# ProDoc_TweenWave_2026-01-04.net
KiCad netlist of a schematic drawn in EasyEDA Pro
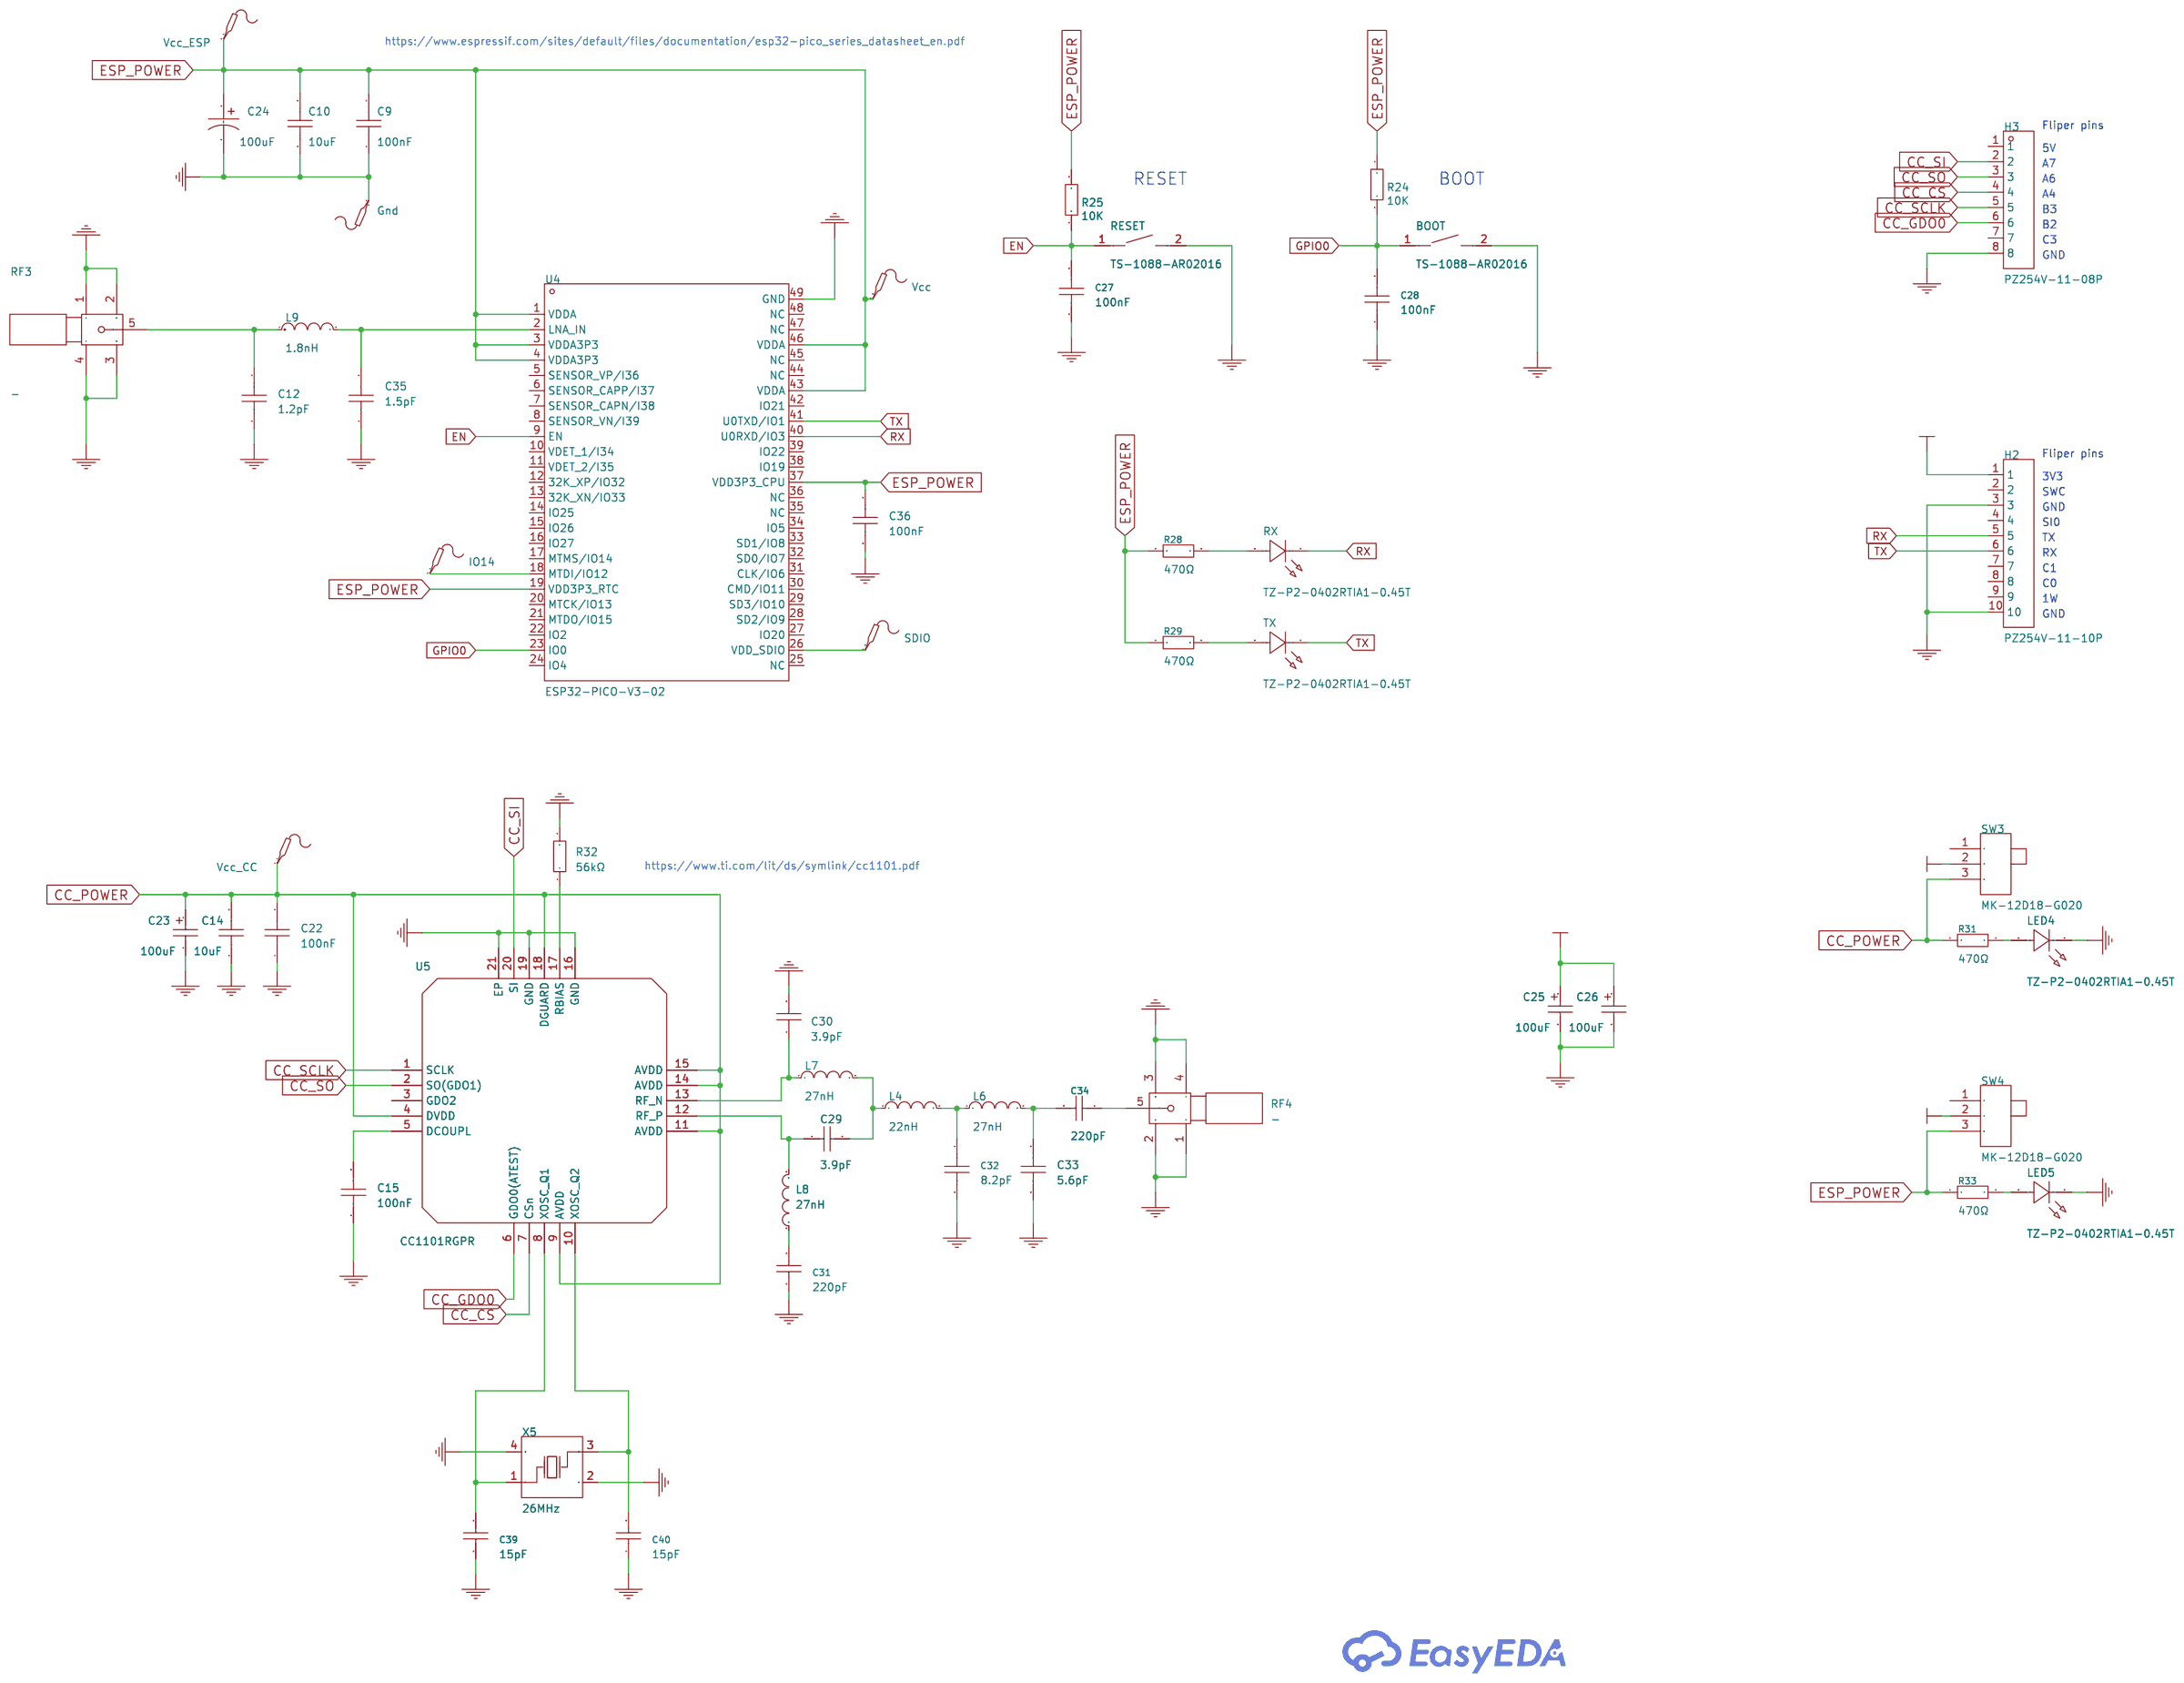
[diagram p0: schematic sheet]

(export (version "E")
  (design (tool "Eeschema 10.0.6"))
  (components
    (comp (ref "BOOT")
      (value "TS-1088-AR02016")
      (footprint "easyedapro:SW-SMD_L3.9-W3.0-P4.45")
      (fields (field (name "Manufacturer") "XUNPU(讯普)"))
      (libsource (lib "easyedapro") (part "TS-1088-AR02016"))
    )
    (comp (ref "C9")
      (value "100nF")
      (footprint "easyedapro:C0603")
      (description "Capacitance:100nF Tolerance:±10% Tolerance:±10% Voltage Rating:50V Temperature Coefficient:X7R")
      (fields
        (field (name "Manufacturer Part") "CC0603KRX7R9BB104")
        (field (name "Manufacturer") "YAGEO(国巨)")
      )
      (libsource (lib "easyedapro") (part "CC0603KRX7R9BB104"))
    )
    (comp (ref "C10")
      (value "10uF")
      (footprint "easyedapro:C0603")
      (fields
        (field (name "Manufacturer Part") "CL10A106MP8NNNC")
        (field (name "Manufacturer") "SAMSUNG(三星)")
      )
      (libsource (lib "easyedapro") (part "CL10A106MP8NNNC"))
    )
    (comp (ref "C12")
      (value "1.2pF")
      (footprint "easyedapro:C0201")
      (fields
        (field (name "Manufacturer Part") "GRM0335C1H1R2BA01D")
        (field (name "Manufacturer") "muRata(村田)")
      )
      (libsource (lib "easyedapro") (part "GRM0335C1H1R2BA01D"))
    )
    (comp (ref "C14")
      (value "10uF")
      (footprint "easyedapro:C0603")
      (fields
        (field (name "Manufacturer Part") "CL10A106MP8NNNC")
        (field (name "Manufacturer") "SAMSUNG(三星)")
      )
      (libsource (lib "easyedapro") (part "CL10A106MP8NNNC"))
    )
    (comp (ref "C15")
      (value "100nF")
      (footprint "easyedapro:C0603")
      (description "Capacitance:100nF Tolerance:±10% Tolerance:±10% Voltage Rating:50V Temperature Coefficient:X7R")
      (fields
        (field (name "Manufacturer Part") "CC0603KRX7R9BB104")
        (field (name "Manufacturer") "YAGEO(国巨)")
      )
      (libsource (lib "easyedapro") (part "CC0603KRX7R9BB104"))
    )
    (comp (ref "C22")
      (value "100nF")
      (footprint "easyedapro:C0603")
      (description "Capacitance:100nF Tolerance:±10% Tolerance:±10% Voltage Rating:50V Temperature Coefficient:X7R")
      (fields
        (field (name "Manufacturer Part") "CC0603KRX7R9BB104")
        (field (name "Manufacturer") "YAGEO(国巨)")
      )
      (libsource (lib "easyedapro") (part "CC0603KRX7R9BB104"))
    )
    (comp (ref "C23")
      (value "100uF")
      (footprint "easyedapro:CASE-B_3528")
      (fields (field (name "Manufacturer Part") "TAJB107K006RNJ") (field (name "Manufacturer") "Kyocera AVX"))
      (libsource (lib "easyedapro") (part "TAJB107K006RNJ"))
    )
    (comp (ref "C24")
      (value "100uF")
      (footprint "easyedapro:CASE-B_3528-1")
      (fields
        (field (name "Manufacturer Part") "TPSB107K006R0250")
        (field (name "Manufacturer") "Kyocera AVX")
      )
      (libsource (lib "easyedapro") (part "TPSB107K006R0250"))
    )
    (comp (ref "C25")
      (value "100uF")
      (footprint "easyedapro:CASE-B_3528")
      (fields (field (name "Manufacturer Part") "TAJB107K006RNJ") (field (name "Manufacturer") "Kyocera AVX"))
      (libsource (lib "easyedapro") (part "TAJB107K006RNJ"))
    )
    (comp (ref "C26")
      (value "100uF")
      (footprint "easyedapro:CASE-B_3528")
      (fields (field (name "Manufacturer Part") "TAJB107K006RNJ") (field (name "Manufacturer") "Kyocera AVX"))
      (libsource (lib "easyedapro") (part "TAJB107K006RNJ"))
    )
    (comp (ref "C27")
      (value "100nF")
      (footprint "easyedapro:C0402")
      (fields
        (field (name "Manufacturer Part") "CC0402KRX7R7BB104")
        (field (name "Manufacturer") "YAGEO(国巨)")
      )
      (libsource (lib "easyedapro") (part "CC0402KRX7R7BB104"))
    )
    (comp (ref "C28")
      (value "100nF")
      (footprint "easyedapro:C0402")
      (fields
        (field (name "Manufacturer Part") "CC0402KRX7R7BB104")
        (field (name "Manufacturer") "YAGEO(国巨)")
      )
      (libsource (lib "easyedapro") (part "CC0402KRX7R7BB104"))
    )
    (comp (ref "C29")
      (value "3.9pF")
      (footprint "easyedapro:C0402")
      (fields (field (name "Manufacturer Part") "0402CG3R9C500NT") (field (name "Manufacturer") "FH(风华)"))
      (libsource (lib "easyedapro") (part "0402CG3R9C500NT"))
    )
    (comp (ref "C30")
      (value "3.9pF")
      (footprint "easyedapro:C0402")
      (fields (field (name "Manufacturer Part") "0402CG3R9C500NT") (field (name "Manufacturer") "FH(风华)"))
      (libsource (lib "easyedapro") (part "0402CG3R9C500NT"))
    )
    (comp (ref "C31")
      (value "220pF")
      (footprint "easyedapro:C0402")
      (description "Capacitance:220pF Tolerance:±5% Tolerance:±5% Voltage Rating:50V Temperature Coefficient:NP0")
      (fields
        (field (name "Manufacturer Part") "CC0402JRNPO9BN221")
        (field (name "Manufacturer") "YAGEO(国巨)")
      )
      (libsource (lib "easyedapro") (part "CC0402JRNPO9BN221"))
    )
    (comp (ref "C32")
      (value "8.2pF")
      (footprint "easyedapro:C0402")
      (fields
        (field (name "Manufacturer Part") "CC0402BRNPO9BN8R2")
        (field (name "Manufacturer") "YAGEO(国巨)")
      )
      (libsource (lib "easyedapro") (part "CC0402BRNPO9BN8R2"))
    )
    (comp (ref "C33")
      (value "5.6pF")
      (footprint "easyedapro:C0402")
      (fields
        (field (name "Manufacturer Part") "CC0402BRNPO9BN5R6")
        (field (name "Manufacturer") "YAGEO(国巨)")
      )
      (libsource (lib "easyedapro") (part "CC0402BRNPO9BN5R6"))
    )
    (comp (ref "C34")
      (value "220pF")
      (footprint "easyedapro:C0402")
      (description "Capacitance:220pF Tolerance:±5% Tolerance:±5% Voltage Rating:50V Temperature Coefficient:NP0")
      (fields
        (field (name "Manufacturer Part") "CC0402JRNPO9BN221")
        (field (name "Manufacturer") "YAGEO(国巨)")
      )
      (libsource (lib "easyedapro") (part "CC0402JRNPO9BN221"))
    )
    (comp (ref "C35")
      (value "1.5pF")
      (footprint "easyedapro:C0201")
      (fields
        (field (name "Manufacturer Part") "GRM0335C1H1R5BA01D")
        (field (name "Manufacturer") "muRata(村田)")
      )
      (libsource (lib "easyedapro") (part "GRM0335C1H1R5BA01D"))
    )
    (comp (ref "C36")
      (value "100nF")
      (footprint "easyedapro:C0603")
      (description "Capacitance:100nF Tolerance:±10% Tolerance:±10% Voltage Rating:50V Temperature Coefficient:X7R")
      (fields
        (field (name "Manufacturer Part") "CC0603KRX7R9BB104")
        (field (name "Manufacturer") "YAGEO(国巨)")
      )
      (libsource (lib "easyedapro") (part "CC0603KRX7R9BB104"))
    )
    (comp (ref "C39")
      (value "15pF")
      (footprint "easyedapro:C0402")
      (fields
        (field (name "Manufacturer Part") "CC0402JRNPO9BN150")
        (field (name "Manufacturer") "YAGEO(国巨)")
      )
      (libsource (lib "easyedapro") (part "CC0402JRNPO9BN150"))
    )
    (comp (ref "C40")
      (value "15pF")
      (footprint "easyedapro:C0402")
      (fields
        (field (name "Manufacturer Part") "CC0402JRNPO9BN150")
        (field (name "Manufacturer") "YAGEO(国巨)")
      )
      (libsource (lib "easyedapro") (part "CC0402JRNPO9BN150"))
    )
    (comp (ref "Gnd")
      (value "~")
      (footprint "easyedapro:Test-Point-0.5mm")
      (description "Test Point 测试点")
      (libsource (lib "easyedapro") (part "Test-Point"))
    )
    (comp (ref "H2")
      (value "PZ254V-11-10P")
      (footprint "easyedapro:HDR-TH_10P-P2.54-V-M")
      (fields (field (name "Manufacturer") "XFCN(兴飞)"))
      (libsource (lib "easyedapro") (part "PZ254V-11-10P"))
    )
    (comp (ref "H3")
      (value "PZ254V-11-08P")
      (footprint "easyedapro:HDR-TH_8P-P2.54-V-M")
      (fields (field (name "Manufacturer") "XFCN(兴飞)"))
      (libsource (lib "easyedapro") (part "PZ254V-11-08P"))
    )
    (comp (ref "IO14")
      (value "~")
      (footprint "easyedapro:Test-Point-0.5mm")
      (description "Test Point 测试点")
      (libsource (lib "easyedapro") (part "Test-Point"))
    )
    (comp (ref "L4")
      (value "22nH")
      (footprint "easyedapro:L0402")
      (fields (field (name "Manufacturer Part") "LQG15HS22NJ02D") (field (name "Manufacturer") "muRata(村田)"))
      (libsource (lib "easyedapro") (part "LQG15HS22NJ02D"))
    )
    (comp (ref "L6")
      (value "27nH")
      (footprint "easyedapro:L0402-RD")
      (fields (field (name "Manufacturer Part") "LQG15HS27NJ02D") (field (name "Manufacturer") "muRata(村田)"))
      (libsource (lib "easyedapro") (part "LQG15HS27NJ02D"))
    )
    (comp (ref "L7")
      (value "27nH")
      (footprint "easyedapro:L0402-RD")
      (fields (field (name "Manufacturer Part") "LQG15HS27NJ02D") (field (name "Manufacturer") "muRata(村田)"))
      (libsource (lib "easyedapro") (part "LQG15HS27NJ02D"))
    )
    (comp (ref "L8")
      (value "27nH")
      (footprint "easyedapro:L0402-RD")
      (fields (field (name "Manufacturer Part") "LQG15HS27NJ02D") (field (name "Manufacturer") "muRata(村田)"))
      (libsource (lib "easyedapro") (part "LQG15HS27NJ02D"))
    )
    (comp (ref "L9")
      (value "1.8nH")
      (footprint "easyedapro:L0201-RD")
      (fields (field (name "Manufacturer Part") "LQP03TN1N8B02D") (field (name "Manufacturer") "muRata(村田)"))
      (libsource (lib "easyedapro") (part "LQP03TN1N8B02D"))
    )
    (comp (ref "LED4")
      (value "TZ-P2-0402RTIA1-0.45T")
      (footprint "easyedapro:LED0402-RD_RED")
      (fields (field (name "Manufacturer") "TUOZHAN(拓展光电)"))
      (libsource (lib "easyedapro") (part "TZ-P2-0402RTIA1-0.45T"))
    )
    (comp (ref "LED5")
      (value "TZ-P2-0402RTIA1-0.45T")
      (footprint "easyedapro:LED0402-RD_RED")
      (fields (field (name "Manufacturer") "TUOZHAN(拓展光电)"))
      (libsource (lib "easyedapro") (part "TZ-P2-0402RTIA1-0.45T"))
    )
    (comp (ref "R24")
      (value "10K")
      (footprint "easyedapro:R0603")
      (fields (field (name "Manufacturer Part") "RC0603DR-0710KL") (field (name "Manufacturer") "YAGEO(国巨)"))
      (libsource (lib "easyedapro") (part "10K"))
    )
    (comp (ref "R25")
      (value "10K")
      (footprint "easyedapro:R0603")
      (fields (field (name "Manufacturer Part") "RC0603DR-0710KL") (field (name "Manufacturer") "YAGEO(国巨)"))
      (libsource (lib "easyedapro") (part "10K"))
    )
    (comp (ref "R28")
      (value "470Ω")
      (footprint "easyedapro:R0402")
      (fields
        (field (name "Manufacturer Part") "0402WGF4700TCE")
        (field (name "Manufacturer") "UNI-ROYAL(厚声)")
      )
      (libsource (lib "easyedapro") (part "0402WGF4700TCE"))
    )
    (comp (ref "R29")
      (value "470Ω")
      (footprint "easyedapro:R0402")
      (fields
        (field (name "Manufacturer Part") "0402WGF4700TCE")
        (field (name "Manufacturer") "UNI-ROYAL(厚声)")
      )
      (libsource (lib "easyedapro") (part "0402WGF4700TCE"))
    )
    (comp (ref "R31")
      (value "470Ω")
      (footprint "easyedapro:R0402")
      (fields
        (field (name "Manufacturer Part") "0402WGF4700TCE")
        (field (name "Manufacturer") "UNI-ROYAL(厚声)")
      )
      (libsource (lib "easyedapro") (part "0402WGF4700TCE"))
    )
    (comp (ref "R32")
      (value "56kΩ")
      (footprint "easyedapro:R0402")
      (fields
        (field (name "Manufacturer Part") "0402WGF5602TCE")
        (field (name "Manufacturer") "UNI-ROYAL(厚声)")
      )
      (libsource (lib "easyedapro") (part "0402WGF5602TCE"))
    )
    (comp (ref "R33")
      (value "470Ω")
      (footprint "easyedapro:R0402")
      (fields
        (field (name "Manufacturer Part") "0402WGF4700TCE")
        (field (name "Manufacturer") "UNI-ROYAL(厚声)")
      )
      (libsource (lib "easyedapro") (part "0402WGF4700TCE"))
    )
    (comp (ref "RESET")
      (value "TS-1088-AR02016")
      (footprint "easyedapro:SW-SMD_L3.9-W3.0-P4.45")
      (fields (field (name "Manufacturer") "XUNPU(讯普)"))
      (libsource (lib "easyedapro") (part "TS-1088-AR02016"))
    )
    (comp (ref "RF3")
      (value "-")
      (footprint "easyedapro:SMA-SMD_BWSMA-KE-P001")
      (fields
        (field (name "Manufacturer Part") "BWSMA-KE-P001")
        (field (name "Manufacturer") "BAT WIRELESS(蝙蝠无线)")
      )
      (libsource (lib "easyedapro") (part "BWSMA-KE-P001"))
    )
    (comp (ref "RF4")
      (value "-")
      (footprint "easyedapro:SMA-SMD_BWSMA-KE-P001")
      (fields
        (field (name "Manufacturer Part") "BWSMA-KE-P001")
        (field (name "Manufacturer") "BAT WIRELESS(蝙蝠无线)")
      )
      (libsource (lib "easyedapro") (part "BWSMA-KE-P001"))
    )
    (comp (ref "RX")
      (value "TZ-P2-0402RTIA1-0.45T")
      (footprint "easyedapro:LED0402-RD_RED")
      (fields (field (name "Manufacturer") "TUOZHAN(拓展光电)"))
      (libsource (lib "easyedapro") (part "TZ-P2-0402RTIA1-0.45T"))
    )
    (comp (ref "SDIO")
      (value "~")
      (footprint "easyedapro:Test-Point-0.5mm")
      (description "Test Point 测试点")
      (libsource (lib "easyedapro") (part "Test-Point"))
    )
    (comp (ref "SW3")
      (value "MK-12D18-G020")
      (footprint "easyedapro:SW-TH_MK-12D18-G040")
      (fields (field (name "Manufacturer") "G-Switch(品赞)"))
      (libsource (lib "easyedapro") (part "MK-12D18-G020"))
    )
    (comp (ref "SW4")
      (value "MK-12D18-G020")
      (footprint "easyedapro:SW-TH_MK-12D18-G040")
      (fields (field (name "Manufacturer") "G-Switch(品赞)"))
      (libsource (lib "easyedapro") (part "MK-12D18-G020"))
    )
    (comp (ref "TX")
      (value "TZ-P2-0402RTIA1-0.45T")
      (footprint "easyedapro:LED0402-RD_RED")
      (fields (field (name "Manufacturer") "TUOZHAN(拓展光电)"))
      (libsource (lib "easyedapro") (part "TZ-P2-0402RTIA1-0.45T"))
    )
    (comp (ref "U4")
      (value "ESP32-PICO-V3-02")
      (footprint "easyedapro:QFN-48_L7.0-W7.0-P0.50-BL-EP5.1")
      (fields (field (name "Manufacturer") "ESPRESSIF(乐鑫)"))
      (libsource (lib "easyedapro") (part "ESP32-PICO-V3-02"))
    )
    (comp (ref "U5")
      (value "CC1101RGPR")
      (footprint "easyedapro:QFN-20_L4.0-W4.0-P0.5-TL-EP")
      (fields (field (name "Manufacturer") "TI(德州仪器)"))
      (libsource (lib "easyedapro") (part "CC1101RGPR"))
    )
    (comp (ref "Vcc")
      (value "~")
      (footprint "easyedapro:Test-Point-0.5mm")
      (description "Test Point 测试点")
      (libsource (lib "easyedapro") (part "Test-Point"))
    )
    (comp (ref "Vcc_CC")
      (value "~")
      (footprint "easyedapro:Test-Point-0.5mm")
      (description "Test Point 测试点")
      (libsource (lib "easyedapro") (part "Test-Point"))
    )
    (comp (ref "Vcc_ESP")
      (value "~")
      (footprint "easyedapro:Test-Point-0.5mm")
      (description "Test Point 测试点")
      (libsource (lib "easyedapro") (part "Test-Point"))
    )
    (comp (ref "X5")
      (value "26MHz")
      (footprint "easyedapro:CRYSTAL-SMD_4P-L3.2-W2.5-BL")
      (fields (field (name "Manufacturer Part") "X322526MMB4SI") (field (name "Manufacturer") "YXC(扬兴晶振)"))
      (libsource (lib "easyedapro") (part "X322526MMB4SI"))
    )
  )
  (nets
    (net (code "1") (name "3V3") (class "Default")
      (node (ref "C25") (pin "1") (pinfunction "1_1") (pintype "input"))
      (node (ref "C26") (pin "1") (pinfunction "1_1") (pintype "input"))
      (node (ref "H2") (pin "1") (pinfunction "1_1") (pintype "unspecified"))
      (node (ref "SW3") (pin "2") (pinfunction "2_2") (pintype "unspecified"))
      (node (ref "SW4") (pin "2") (pinfunction "2_2") (pintype "unspecified"))
    )
    (net (code "2") (name "CC_CS") (class "Default")
      (node (ref "H3") (pin "4") (pinfunction "4_4") (pintype "unspecified"))
      (node (ref "U5") (pin "7") (pinfunction "CSn_7") (pintype "unspecified"))
    )
    (net (code "3") (name "CC_GDO0") (class "Default")
      (node (ref "H3") (pin "6") (pinfunction "6_6") (pintype "unspecified"))
      (node (ref "U5") (pin "6") (pinfunction "GDO0(ATEST)_6") (pintype "unspecified"))
    )
    (net (code "4") (name "CC_POWER") (class "Default")
      (node (ref "C14") (pin "2") (pinfunction "2_2") (pintype "unspecified"))
      (node (ref "C22") (pin "2") (pinfunction "2_2") (pintype "unspecified"))
      (node (ref "C23") (pin "1") (pinfunction "1_1") (pintype "input"))
      (node (ref "R31") (pin "1") (pinfunction "1_1") (pintype "input"))
      (node (ref "SW3") (pin "3") (pinfunction "3_3") (pintype "unspecified"))
      (node (ref "U5") (pin "11") (pinfunction "AVDD_11") (pintype "unspecified"))
      (node (ref "U5") (pin "14") (pinfunction "AVDD_14") (pintype "unspecified"))
      (node (ref "U5") (pin "15") (pinfunction "AVDD_15") (pintype "unspecified"))
      (node (ref "U5") (pin "18") (pinfunction "DGUARD_18") (pintype "unspecified"))
      (node (ref "U5") (pin "4") (pinfunction "DVDD_4") (pintype "unspecified"))
      (node (ref "U5") (pin "9") (pinfunction "AVDD_9") (pintype "unspecified"))
      (node (ref "Vcc_CC") (pin "1") (pinfunction "1_1") (pintype "unspecified"))
    )
    (net (code "5") (name "CC_SCLK") (class "Default")
      (node (ref "H3") (pin "5") (pinfunction "5_5") (pintype "unspecified"))
      (node (ref "U5") (pin "1") (pinfunction "SCLK_1") (pintype "unspecified"))
    )
    (net (code "6") (name "CC_SI") (class "Default")
      (node (ref "H3") (pin "2") (pinfunction "2_2") (pintype "unspecified"))
      (node (ref "U5") (pin "20") (pinfunction "SI_20") (pintype "unspecified"))
    )
    (net (code "7") (name "CC_SO") (class "Default")
      (node (ref "H3") (pin "3") (pinfunction "3_3") (pintype "unspecified"))
      (node (ref "U5") (pin "2") (pinfunction "SO(GDO1)_2") (pintype "unspecified"))
    )
    (net (code "8") (name "EN") (class "Default")
      (node (ref "C27") (pin "2") (pinfunction "2_2") (pintype "input"))
      (node (ref "R25") (pin "1") (pinfunction "1_1") (pintype "input"))
      (node (ref "RESET") (pin "1") (pinfunction "1_1") (pintype "unspecified"))
      (node (ref "U4") (pin "9") (pinfunction "EN_9") (pintype "unspecified"))
    )
    (net (code "9") (name "ESP_POWER") (class "Default")
      (node (ref "C10") (pin "2") (pinfunction "2_2") (pintype "unspecified"))
      (node (ref "C24") (pin "1") (pinfunction "1_1") (pintype "unspecified"))
      (node (ref "C36") (pin "2") (pinfunction "2_2") (pintype "unspecified"))
      (node (ref "C9") (pin "2") (pinfunction "2_2") (pintype "unspecified"))
      (node (ref "R24") (pin "2") (pinfunction "2_2") (pintype "input"))
      (node (ref "R25") (pin "2") (pinfunction "2_2") (pintype "input"))
      (node (ref "R28") (pin "1") (pinfunction "1_1") (pintype "input"))
      (node (ref "R29") (pin "1") (pinfunction "1_1") (pintype "input"))
      (node (ref "R33") (pin "1") (pinfunction "1_1") (pintype "input"))
      (node (ref "SW4") (pin "3") (pinfunction "3_3") (pintype "unspecified"))
      (node (ref "U4") (pin "1") (pinfunction "VDDA_1") (pintype "unspecified"))
      (node (ref "U4") (pin "19") (pinfunction "VDD3P3_RTC_19") (pintype "unspecified"))
      (node (ref "U4") (pin "3") (pinfunction "VDDA3P3_3") (pintype "unspecified"))
      (node (ref "U4") (pin "37") (pinfunction "VDD3P3_CPU_37") (pintype "unspecified"))
      (node (ref "U4") (pin "4") (pinfunction "VDDA3P3_4") (pintype "unspecified"))
      (node (ref "U4") (pin "43") (pinfunction "VDDA_43") (pintype "unspecified"))
      (node (ref "U4") (pin "46") (pinfunction "VDDA_46") (pintype "unspecified"))
      (node (ref "Vcc") (pin "1") (pinfunction "1_1") (pintype "unspecified"))
      (node (ref "Vcc_ESP") (pin "1") (pinfunction "1_1") (pintype "unspecified"))
    )
    (net (code "10") (name "GND") (class "Default")
      (node (ref "BOOT") (pin "2") (pinfunction "2_2") (pintype "unspecified"))
      (node (ref "C10") (pin "1") (pinfunction "1_1") (pintype "unspecified"))
      (node (ref "C12") (pin "1") (pinfunction "1_1") (pintype "unspecified"))
      (node (ref "C14") (pin "1") (pinfunction "1_1") (pintype "unspecified"))
      (node (ref "C15") (pin "1") (pinfunction "1_1") (pintype "unspecified"))
      (node (ref "C22") (pin "1") (pinfunction "1_1") (pintype "unspecified"))
      (node (ref "C23") (pin "2") (pinfunction "2_2") (pintype "input"))
      (node (ref "C24") (pin "2") (pinfunction "2_2") (pintype "unspecified"))
      (node (ref "C25") (pin "2") (pinfunction "2_2") (pintype "input"))
      (node (ref "C26") (pin "2") (pinfunction "2_2") (pintype "input"))
      (node (ref "C27") (pin "1") (pinfunction "1_1") (pintype "input"))
      (node (ref "C28") (pin "1") (pinfunction "1_1") (pintype "input"))
      (node (ref "C30") (pin "2") (pinfunction "2_2") (pintype "input"))
      (node (ref "C31") (pin "1") (pinfunction "1_1") (pintype "input"))
      (node (ref "C32") (pin "2") (pinfunction "2_2") (pintype "input"))
      (node (ref "C33") (pin "1") (pinfunction "1_1") (pintype "unspecified"))
      (node (ref "C35") (pin "1") (pinfunction "1_1") (pintype "unspecified"))
      (node (ref "C36") (pin "1") (pinfunction "1_1") (pintype "unspecified"))
      (node (ref "C39") (pin "1") (pinfunction "1_1") (pintype "input"))
      (node (ref "C40") (pin "1") (pinfunction "1_1") (pintype "input"))
      (node (ref "C9") (pin "1") (pinfunction "1_1") (pintype "unspecified"))
      (node (ref "Gnd") (pin "1") (pinfunction "1_1") (pintype "unspecified"))
      (node (ref "H2") (pin "10") (pinfunction "10_10") (pintype "unspecified"))
      (node (ref "H2") (pin "3") (pinfunction "3_3") (pintype "unspecified"))
      (node (ref "H3") (pin "8") (pinfunction "8_8") (pintype "unspecified"))
      (node (ref "LED4") (pin "1") (pinfunction "K_1") (pintype "unspecified"))
      (node (ref "LED5") (pin "1") (pinfunction "K_1") (pintype "unspecified"))
      (node (ref "R32") (pin "2") (pinfunction "2_2") (pintype "input"))
      (node (ref "RESET") (pin "2") (pinfunction "2_2") (pintype "unspecified"))
      (node (ref "RF3") (pin "1") (pinfunction "1_1") (pintype "unspecified"))
      (node (ref "RF3") (pin "2") (pinfunction "2_2") (pintype "unspecified"))
      (node (ref "RF3") (pin "3") (pinfunction "3_3") (pintype "unspecified"))
      (node (ref "RF3") (pin "4") (pinfunction "4_4") (pintype "unspecified"))
      (node (ref "RF4") (pin "1") (pinfunction "1_1") (pintype "unspecified"))
      (node (ref "RF4") (pin "2") (pinfunction "2_2") (pintype "unspecified"))
      (node (ref "RF4") (pin "3") (pinfunction "3_3") (pintype "unspecified"))
      (node (ref "RF4") (pin "4") (pinfunction "4_4") (pintype "unspecified"))
      (node (ref "U4") (pin "49") (pinfunction "GND_49") (pintype "unspecified"))
      (node (ref "U5") (pin "16") (pinfunction "GND_16") (pintype "unspecified"))
      (node (ref "U5") (pin "19") (pinfunction "GND_19") (pintype "unspecified"))
      (node (ref "U5") (pin "21") (pinfunction "EP_21") (pintype "unspecified"))
      (node (ref "X5") (pin "2") (pinfunction "GND_2") (pintype "unspecified"))
      (node (ref "X5") (pin "4") (pinfunction "GND_4") (pintype "unspecified"))
    )
    (net (code "11") (name "GPIO0") (class "Default")
      (node (ref "BOOT") (pin "1") (pinfunction "1_1") (pintype "unspecified"))
      (node (ref "C28") (pin "2") (pinfunction "2_2") (pintype "input"))
      (node (ref "R24") (pin "1") (pinfunction "1_1") (pintype "input"))
      (node (ref "U4") (pin "23") (pinfunction "IO0_23") (pintype "unspecified"))
    )
    (net (code "12") (name "Net-(C12-Pad2)") (class "Default")
      (node (ref "C12") (pin "2") (pinfunction "2_2") (pintype "unspecified"))
      (node (ref "L9") (pin "1") (pinfunction "1_1") (pintype "input"))
      (node (ref "RF3") (pin "5") (pinfunction "5_5") (pintype "unspecified"))
    )
    (net (code "13") (name "Net-(C29-Pad2)") (class "Default")
      (node (ref "C29") (pin "2") (pinfunction "2_2") (pintype "input"))
      (node (ref "L4") (pin "1") (pinfunction "1_1") (pintype "unspecified"))
      (node (ref "L7") (pin "2") (pinfunction "2_2") (pintype "unspecified"))
    )
    (net (code "14") (name "Net-(C31-Pad2)") (class "Default")
      (node (ref "C31") (pin "2") (pinfunction "2_2") (pintype "input"))
      (node (ref "L8") (pin "1") (pinfunction "1_1") (pintype "unspecified"))
    )
    (net (code "15") (name "Net-(C32-Pad1)") (class "Default")
      (node (ref "C32") (pin "1") (pinfunction "1_1") (pintype "input"))
      (node (ref "L4") (pin "2") (pinfunction "2_2") (pintype "unspecified"))
      (node (ref "L6") (pin "1") (pinfunction "1_1") (pintype "unspecified"))
    )
    (net (code "16") (name "Net-(C33-Pad2)") (class "Default")
      (node (ref "C33") (pin "2") (pinfunction "2_2") (pintype "unspecified"))
      (node (ref "C34") (pin "2") (pinfunction "2_2") (pintype "input"))
      (node (ref "L6") (pin "2") (pinfunction "2_2") (pintype "unspecified"))
    )
    (net (code "17") (name "Net-(C34-Pad1)") (class "Default")
      (node (ref "C34") (pin "1") (pinfunction "1_1") (pintype "input"))
      (node (ref "RF4") (pin "5") (pinfunction "5_5") (pintype "unspecified"))
    )
    (net (code "18") (name "Net-(LED4-A)") (class "Default")
      (node (ref "LED4") (pin "2") (pinfunction "A_2") (pintype "unspecified"))
      (node (ref "R31") (pin "2") (pinfunction "2_2") (pintype "input"))
    )
    (net (code "19") (name "Net-(LED5-A)") (class "Default")
      (node (ref "LED5") (pin "2") (pinfunction "A_2") (pintype "unspecified"))
      (node (ref "R33") (pin "2") (pinfunction "2_2") (pintype "input"))
    )
    (net (code "20") (name "Net-(RX-A)") (class "Default")
      (node (ref "R28") (pin "2") (pinfunction "2_2") (pintype "input"))
      (node (ref "RX") (pin "2") (pinfunction "A_2") (pintype "unspecified"))
    )
    (net (code "21") (name "Net-(TX-A)") (class "Default")
      (node (ref "R29") (pin "2") (pinfunction "2_2") (pintype "input"))
      (node (ref "TX") (pin "2") (pinfunction "A_2") (pintype "unspecified"))
    )
    (net (code "22") (name "Net-(U4-LNA_IN)") (class "Default")
      (node (ref "C35") (pin "2") (pinfunction "2_2") (pintype "unspecified"))
      (node (ref "L9") (pin "2") (pinfunction "2_2") (pintype "input"))
      (node (ref "U4") (pin "2") (pinfunction "LNA_IN_2") (pintype "unspecified"))
    )
    (net (code "23") (name "Net-(U4-MTDI{slash}IO12)") (class "Default")
      (node (ref "IO14") (pin "1") (pinfunction "1_1") (pintype "unspecified"))
      (node (ref "U4") (pin "18") (pinfunction "MTDI/IO12_18") (pintype "unspecified"))
    )
    (net (code "24") (name "Net-(U4-VDD_SDIO)") (class "Default")
      (node (ref "SDIO") (pin "1") (pinfunction "1_1") (pintype "unspecified"))
      (node (ref "U4") (pin "26") (pinfunction "VDD_SDIO_26") (pintype "unspecified"))
    )
    (net (code "25") (name "Net-(U5-DCOUPL)") (class "Default")
      (node (ref "C15") (pin "2") (pinfunction "2_2") (pintype "unspecified"))
      (node (ref "U5") (pin "5") (pinfunction "DCOUPL_5") (pintype "unspecified"))
    )
    (net (code "26") (name "Net-(U5-RBIAS)") (class "Default")
      (node (ref "R32") (pin "1") (pinfunction "1_1") (pintype "input"))
      (node (ref "U5") (pin "17") (pinfunction "RBIAS_17") (pintype "unspecified"))
    )
    (net (code "27") (name "Net-(U5-RF_N)") (class "Default")
      (node (ref "C30") (pin "1") (pinfunction "1_1") (pintype "input"))
      (node (ref "L7") (pin "1") (pinfunction "1_1") (pintype "unspecified"))
      (node (ref "U5") (pin "13") (pinfunction "RF_N_13") (pintype "unspecified"))
    )
    (net (code "28") (name "Net-(U5-RF_P)") (class "Default")
      (node (ref "C29") (pin "1") (pinfunction "1_1") (pintype "input"))
      (node (ref "L8") (pin "2") (pinfunction "2_2") (pintype "unspecified"))
      (node (ref "U5") (pin "12") (pinfunction "RF_P_12") (pintype "unspecified"))
    )
    (net (code "29") (name "Net-(U5-XOSC_Q1)") (class "Default")
      (node (ref "C39") (pin "2") (pinfunction "2_2") (pintype "input"))
      (node (ref "U5") (pin "8") (pinfunction "XOSC_Q1_8") (pintype "unspecified"))
      (node (ref "X5") (pin "1") (pinfunction "OSC1_1") (pintype "unspecified"))
    )
    (net (code "30") (name "Net-(U5-XOSC_Q2)") (class "Default")
      (node (ref "C40") (pin "2") (pinfunction "2_2") (pintype "input"))
      (node (ref "U5") (pin "10") (pinfunction "XOSC_Q2_10") (pintype "unspecified"))
      (node (ref "X5") (pin "3") (pinfunction "OSC2_3") (pintype "unspecified"))
    )
    (net (code "31") (name "RX") (class "Default")
      (node (ref "H2") (pin "5") (pinfunction "5_5") (pintype "unspecified"))
      (node (ref "RX") (pin "1") (pinfunction "K_1") (pintype "unspecified"))
      (node (ref "U4") (pin "40") (pinfunction "U0RXD/IO3_40") (pintype "unspecified"))
    )
    (net (code "32") (name "TX") (class "Default")
      (node (ref "H2") (pin "6") (pinfunction "6_6") (pintype "unspecified"))
      (node (ref "TX") (pin "1") (pinfunction "K_1") (pintype "unspecified"))
      (node (ref "U4") (pin "41") (pinfunction "U0TXD/IO1_41") (pintype "unspecified"))
    )
    (net (code "33") (name "unconnected-(H2-Pad2)") (class "Default")
      (node (ref "H2") (pin "2") (pinfunction "2_2") (pintype "unspecified"))
    )
    (net (code "34") (name "unconnected-(H2-Pad4)") (class "Default")
      (node (ref "H2") (pin "4") (pinfunction "4_4") (pintype "unspecified"))
    )
    (net (code "35") (name "unconnected-(H2-Pad7)") (class "Default")
      (node (ref "H2") (pin "7") (pinfunction "7_7") (pintype "unspecified"))
    )
    (net (code "36") (name "unconnected-(H2-Pad8)") (class "Default")
      (node (ref "H2") (pin "8") (pinfunction "8_8") (pintype "unspecified"))
    )
    (net (code "37") (name "unconnected-(H2-Pad9)") (class "Default")
      (node (ref "H2") (pin "9") (pinfunction "9_9") (pintype "unspecified"))
    )
    (net (code "38") (name "unconnected-(H3-Pad1)") (class "Default")
      (node (ref "H3") (pin "1") (pinfunction "1_1") (pintype "unspecified"))
    )
    (net (code "39") (name "unconnected-(H3-Pad7)") (class "Default")
      (node (ref "H3") (pin "7") (pinfunction "7_7") (pintype "unspecified"))
    )
    (net (code "40") (name "unconnected-(SW3-Pad1)") (class "Default")
      (node (ref "SW3") (pin "1") (pinfunction "1_1") (pintype "unspecified"))
    )
    (net (code "41") (name "unconnected-(SW4-Pad1)") (class "Default")
      (node (ref "SW4") (pin "1") (pinfunction "1_1") (pintype "unspecified"))
    )
    (net (code "42") (name "unconnected-(U4-32K_XN{slash}IO33-Pad13)") (class "Default")
      (node (ref "U4") (pin "13") (pinfunction "32K_XN/IO33_13") (pintype "unspecified"))
    )
    (net (code "43") (name "unconnected-(U4-32K_XP{slash}IO32-Pad12)") (class "Default")
      (node (ref "U4") (pin "12") (pinfunction "32K_XP/IO32_12") (pintype "unspecified"))
    )
    (net (code "44") (name "unconnected-(U4-CLK{slash}IO6-Pad31)") (class "Default")
      (node (ref "U4") (pin "31") (pinfunction "CLK/IO6_31") (pintype "unspecified"))
    )
    (net (code "45") (name "unconnected-(U4-CMD{slash}IO11-Pad30)") (class "Default")
      (node (ref "U4") (pin "30") (pinfunction "CMD/IO11_30") (pintype "unspecified"))
    )
    (net (code "46") (name "unconnected-(U4-IO2-Pad22)") (class "Default")
      (node (ref "U4") (pin "22") (pinfunction "IO2_22") (pintype "unspecified"))
    )
    (net (code "47") (name "unconnected-(U4-IO4-Pad24)") (class "Default")
      (node (ref "U4") (pin "24") (pinfunction "IO4_24") (pintype "unspecified"))
    )
    (net (code "48") (name "unconnected-(U4-IO5-Pad34)") (class "Default")
      (node (ref "U4") (pin "34") (pinfunction "IO5_34") (pintype "unspecified"))
    )
    (net (code "49") (name "unconnected-(U4-IO19-Pad38)") (class "Default")
      (node (ref "U4") (pin "38") (pinfunction "IO19_38") (pintype "unspecified"))
    )
    (net (code "50") (name "unconnected-(U4-IO20-Pad27)") (class "Default")
      (node (ref "U4") (pin "27") (pinfunction "IO20_27") (pintype "unspecified"))
    )
    (net (code "51") (name "unconnected-(U4-IO21-Pad42)") (class "Default")
      (node (ref "U4") (pin "42") (pinfunction "IO21_42") (pintype "unspecified"))
    )
    (net (code "52") (name "unconnected-(U4-IO22-Pad39)") (class "Default")
      (node (ref "U4") (pin "39") (pinfunction "IO22_39") (pintype "unspecified"))
    )
    (net (code "53") (name "unconnected-(U4-IO25-Pad14)") (class "Default")
      (node (ref "U4") (pin "14") (pinfunction "IO25_14") (pintype "unspecified"))
    )
    (net (code "54") (name "unconnected-(U4-IO26-Pad15)") (class "Default")
      (node (ref "U4") (pin "15") (pinfunction "IO26_15") (pintype "unspecified"))
    )
    (net (code "55") (name "unconnected-(U4-IO27-Pad16)") (class "Default")
      (node (ref "U4") (pin "16") (pinfunction "IO27_16") (pintype "unspecified"))
    )
    (net (code "56") (name "unconnected-(U4-MTCK{slash}IO13-Pad20)") (class "Default")
      (node (ref "U4") (pin "20") (pinfunction "MTCK/IO13_20") (pintype "unspecified"))
    )
    (net (code "57") (name "unconnected-(U4-MTDO{slash}IO15-Pad21)") (class "Default")
      (node (ref "U4") (pin "21") (pinfunction "MTDO/IO15_21") (pintype "unspecified"))
    )
    (net (code "58") (name "unconnected-(U4-MTMS{slash}IO14-Pad17)") (class "Default")
      (node (ref "U4") (pin "17") (pinfunction "MTMS/IO14_17") (pintype "unspecified"))
    )
    (net (code "59") (name "unconnected-(U4-NC-Pad25)") (class "Default")
      (node (ref "U4") (pin "25") (pinfunction "NC_25") (pintype "unspecified"))
    )
    (net (code "60") (name "unconnected-(U4-NC-Pad35)") (class "Default")
      (node (ref "U4") (pin "35") (pinfunction "NC_35") (pintype "unspecified"))
    )
    (net (code "61") (name "unconnected-(U4-NC-Pad36)") (class "Default")
      (node (ref "U4") (pin "36") (pinfunction "NC_36") (pintype "unspecified"))
    )
    (net (code "62") (name "unconnected-(U4-NC-Pad44)") (class "Default")
      (node (ref "U4") (pin "44") (pinfunction "NC_44") (pintype "unspecified"))
    )
    (net (code "63") (name "unconnected-(U4-NC-Pad45)") (class "Default")
      (node (ref "U4") (pin "45") (pinfunction "NC_45") (pintype "unspecified"))
    )
    (net (code "64") (name "unconnected-(U4-NC-Pad47)") (class "Default")
      (node (ref "U4") (pin "47") (pinfunction "NC_47") (pintype "unspecified"))
    )
    (net (code "65") (name "unconnected-(U4-NC-Pad48)") (class "Default")
      (node (ref "U4") (pin "48") (pinfunction "NC_48") (pintype "unspecified"))
    )
    (net (code "66") (name "unconnected-(U4-SD0{slash}IO7-Pad32)") (class "Default")
      (node (ref "U4") (pin "32") (pinfunction "SD0/IO7_32") (pintype "unspecified"))
    )
    (net (code "67") (name "unconnected-(U4-SD1{slash}IO8-Pad33)") (class "Default")
      (node (ref "U4") (pin "33") (pinfunction "SD1/IO8_33") (pintype "unspecified"))
    )
    (net (code "68") (name "unconnected-(U4-SD2{slash}IO9-Pad28)") (class "Default")
      (node (ref "U4") (pin "28") (pinfunction "SD2/IO9_28") (pintype "unspecified"))
    )
    (net (code "69") (name "unconnected-(U4-SD3{slash}IO10-Pad29)") (class "Default")
      (node (ref "U4") (pin "29") (pinfunction "SD3/IO10_29") (pintype "unspecified"))
    )
    (net (code "70") (name "unconnected-(U4-SENSOR_CAPN{slash}I38-Pad7)") (class "Default")
      (node (ref "U4") (pin "7") (pinfunction "SENSOR_CAPN/I38_7") (pintype "unspecified"))
    )
    (net (code "71") (name "unconnected-(U4-SENSOR_CAPP{slash}I37-Pad6)") (class "Default")
      (node (ref "U4") (pin "6") (pinfunction "SENSOR_CAPP/I37_6") (pintype "unspecified"))
    )
    (net (code "72") (name "unconnected-(U4-SENSOR_VN{slash}I39-Pad8)") (class "Default")
      (node (ref "U4") (pin "8") (pinfunction "SENSOR_VN/I39_8") (pintype "unspecified"))
    )
    (net (code "73") (name "unconnected-(U4-SENSOR_VP{slash}I36-Pad5)") (class "Default")
      (node (ref "U4") (pin "5") (pinfunction "SENSOR_VP/I36_5") (pintype "unspecified"))
    )
    (net (code "74") (name "unconnected-(U4-VDET_1{slash}I34-Pad10)") (class "Default")
      (node (ref "U4") (pin "10") (pinfunction "VDET_1/I34_10") (pintype "unspecified"))
    )
    (net (code "75") (name "unconnected-(U4-VDET_2{slash}I35-Pad11)") (class "Default")
      (node (ref "U4") (pin "11") (pinfunction "VDET_2/I35_11") (pintype "unspecified"))
    )
    (net (code "76") (name "unconnected-(U5-GDO2-Pad3)") (class "Default")
      (node (ref "U5") (pin "3") (pinfunction "GDO2_3") (pintype "unspecified"))
    )
  )
)
